# CHEAPO3.net
KiCad netlist of a schematic drawn in EAGLE
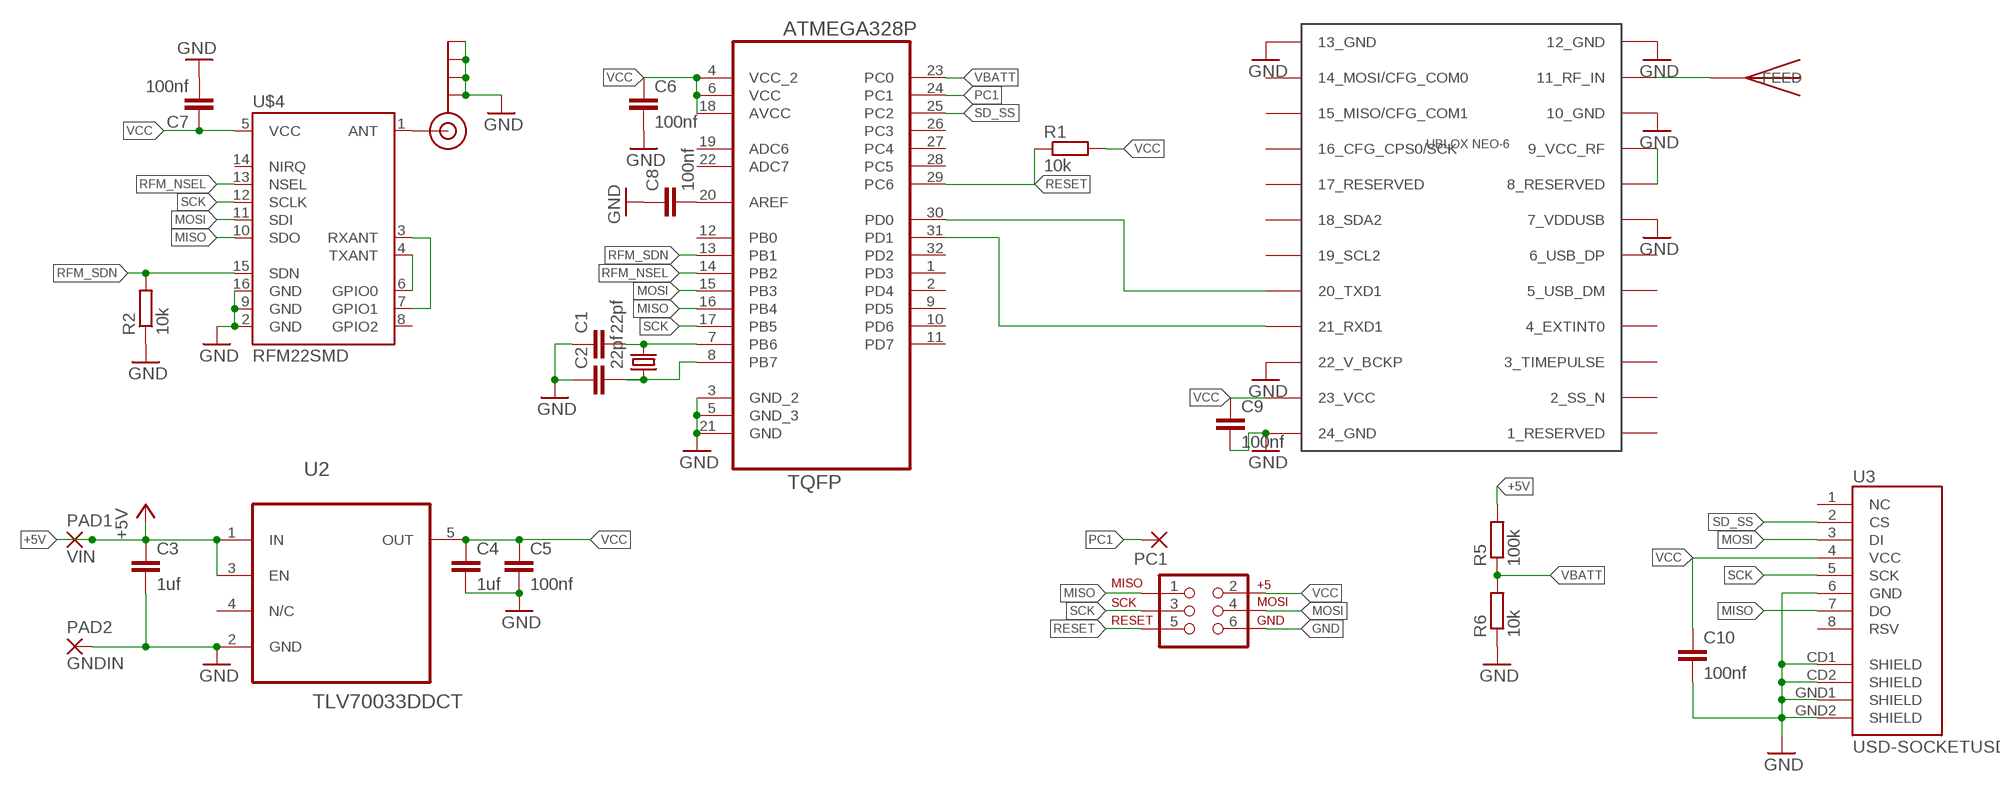
[diagram p0: schematic, sheet 1]

(export (version "E")
  (design (tool "Eeschema 10.0.6"))
  (components
    (comp (ref "C1")
      (value "22pf")
      (footprint "eagle-import:C0603")
      (libsource (lib "eagle-import") (part "C-EUC0603"))
    )
    (comp (ref "C2")
      (value "22pf")
      (footprint "eagle-import:C0603")
      (libsource (lib "eagle-import") (part "C-EUC0603"))
    )
    (comp (ref "C3")
      (value "1uf")
      (footprint "eagle-import:C0603")
      (libsource (lib "eagle-import") (part "C-EUC0603"))
    )
    (comp (ref "C4")
      (value "1uf")
      (footprint "eagle-import:C0603")
      (libsource (lib "eagle-import") (part "C-EUC0603"))
    )
    (comp (ref "C5")
      (value "100nf")
      (footprint "eagle-import:C0603")
      (libsource (lib "eagle-import") (part "C-EUC0603"))
    )
    (comp (ref "C6")
      (value "100nf")
      (footprint "eagle-import:C0603")
      (libsource (lib "eagle-import") (part "C-EUC0603"))
    )
    (comp (ref "C7")
      (value "100nf")
      (footprint "eagle-import:C0603")
      (libsource (lib "eagle-import") (part "C-EUC0603"))
    )
    (comp (ref "C8")
      (value "100nf")
      (footprint "eagle-import:C0603")
      (libsource (lib "eagle-import") (part "C-EUC0603"))
    )
    (comp (ref "C9")
      (value "100nf")
      (footprint "eagle-import:C0603")
      (libsource (lib "eagle-import") (part "C-EUC0603"))
    )
    (comp (ref "C10")
      (value "100nf")
      (footprint "eagle-import:C0603")
      (libsource (lib "eagle-import") (part "C-EUC0603"))
    )
    (comp (ref "J$1")
      (value "SMA_EDGE")
      (footprint "eagle-import:SMA-EDGE")
      (libsource (lib "eagle-import") (part "SMA_EDGE"))
    )
    (comp (ref "J1")
      (value "AVR_SPI_PRG_6PTH")
      (footprint "eagle-import:2X3")
      (libsource (lib "eagle-import") (part "AVR_SPI_PRG_6PTH"))
    )
    (comp (ref "PAD1")
      (value "VIN")
      (footprint "eagle-import:SMD1,27-2,54")
      (libsource (lib "eagle-import") (part "SMD2"))
    )
    (comp (ref "PAD2")
      (value "GNDIN")
      (footprint "eagle-import:SMD1,27-2,54")
      (libsource (lib "eagle-import") (part "SMD2"))
    )
    (comp (ref "PC1")
      (value "SMD2")
      (footprint "eagle-import:SMD1,27-2,54")
      (libsource (lib "eagle-import") (part "SMD2"))
    )
    (comp (ref "R1")
      (value "10k")
      (footprint "eagle-import:R0603")
      (libsource (lib "eagle-import") (part "R-EU_R0603"))
    )
    (comp (ref "R2")
      (value "10k")
      (footprint "eagle-import:R0603")
      (libsource (lib "eagle-import") (part "R-EU_R0603"))
    )
    (comp (ref "R5")
      (value "100k")
      (footprint "eagle-import:R0603")
      (libsource (lib "eagle-import") (part "R-EU_R0603"))
    )
    (comp (ref "R6")
      (value "10k")
      (footprint "eagle-import:R0603")
      (libsource (lib "eagle-import") (part "R-EU_R0603"))
    )
    (comp (ref "U$1")
      (value "UBLOX_NEO-6")
      (footprint "eagle-import:UBLOX_NEO-6P")
      (libsource (lib "eagle-import") (part "UBLOX_NEO-6"))
    )
    (comp (ref "U$2")
      (value "ABRACON_ABM3_CRYSTALABM03_HC49")
      (footprint "eagle-import:ABM03_HC49")
      (libsource (lib "eagle-import") (part "ABRACON_ABM3_CRYSTALABM03_HC49"))
    )
    (comp (ref "U$3")
      (value "JTI_ANTENNA-1575AT43A40")
      (footprint "eagle-import:JTI_ANTENNA-1575AT43A40")
      (libsource (lib "eagle-import") (part "JTI_ANTENNA-1575AT43A40"))
    )
    (comp (ref "U$4")
      (value "RFM22SMD")
      (footprint "eagle-import:RFM22-XXX-S2")
      (libsource (lib "eagle-import") (part "RFM22SMD"))
    )
    (comp (ref "U1")
      (value "ATMEGA328P-AU")
      (footprint "eagle-import:QFP80P900X900X120-32N")
      (libsource (lib "eagle-import") (part "ATMEGA328P-AU"))
    )
    (comp (ref "U2")
      (value "TLV70033DDCT")
      (footprint "eagle-import:SOT95P280X110-5N")
      (libsource (lib "eagle-import") (part "TLV70033DDCT"))
    )
    (comp (ref "U3")
      (value "USD-SOCKETUSD")
      (footprint "eagle-import:USD-SOCKET-PP")
      (libsource (lib "eagle-import") (part "USD-SOCKETUSD"))
    )
  )
  (nets
    (net (code "1") (name "+5V") (class "Default")
      (node (ref "C3") (pin "1") (pinfunction "1_1") (pintype "passive"))
      (node (ref "PAD1") (pin "1") (pinfunction "P_1") (pintype "passive"))
      (node (ref "R5") (pin "2") (pinfunction "2_2") (pintype "passive"))
      (node (ref "U2") (pin "1") (pinfunction "IN_1") (pintype "input"))
      (node (ref "U2") (pin "3") (pinfunction "EN_3") (pintype "input"))
    )
    (net (code "2") (name "GND") (class "Default")
      (node (ref "C1") (pin "1") (pinfunction "1_1") (pintype "passive"))
      (node (ref "C10") (pin "2") (pinfunction "2_2") (pintype "passive"))
      (node (ref "C2") (pin "1") (pinfunction "1_1") (pintype "passive"))
      (node (ref "C3") (pin "2") (pinfunction "2_2") (pintype "passive"))
      (node (ref "C4") (pin "2") (pinfunction "2_2") (pintype "passive"))
      (node (ref "C5") (pin "2") (pinfunction "2_2") (pintype "passive"))
      (node (ref "C6") (pin "2") (pinfunction "2_2") (pintype "passive"))
      (node (ref "C7") (pin "2") (pinfunction "2_2") (pintype "passive"))
      (node (ref "C8") (pin "1") (pinfunction "1_1") (pintype "passive"))
      (node (ref "C9") (pin "2") (pinfunction "2_2") (pintype "passive"))
      (node (ref "J$1") (pin "GND@0") (pinfunction "GND_GND@0") (pintype "bidirectional"))
      (node (ref "J$1") (pin "GND@1") (pinfunction "GND_GND@1") (pintype "bidirectional"))
      (node (ref "J$1") (pin "GND@2") (pinfunction "GND_GND@2") (pintype "bidirectional"))
      (node (ref "J$1") (pin "GND@3") (pinfunction "GND_GND@3") (pintype "bidirectional"))
      (node (ref "J1") (pin "6") (pinfunction "6_6") (pintype "passive"))
      (node (ref "PAD2") (pin "1") (pinfunction "P_1") (pintype "passive"))
      (node (ref "R2") (pin "1") (pinfunction "1_1") (pintype "passive"))
      (node (ref "R6") (pin "1") (pinfunction "1_1") (pintype "passive"))
      (node (ref "U$1") (pin "10_GND") (pinfunction "10_GND_10_GND") (pintype "bidirectional"))
      (node (ref "U$1") (pin "12_GND") (pinfunction "12_GND_12_GND") (pintype "bidirectional"))
      (node (ref "U$1") (pin "13_GND") (pinfunction "13_GND_13_GND") (pintype "bidirectional"))
      (node (ref "U$1") (pin "22_V_BCKP") (pinfunction "22_V_BCKP_22_V_BCKP") (pintype "bidirectional"))
      (node (ref "U$1") (pin "24_GND") (pinfunction "24_GND_24_GND") (pintype "bidirectional"))
      (node (ref "U$1") (pin "7_VDDUSB") (pinfunction "7_VDDUSB_7_VDDUSB") (pintype "bidirectional"))
      (node (ref "U$4") (pin "16") (pinfunction "GND_16") (pintype "power_in"))
      (node (ref "U$4") (pin "2") (pinfunction "GND_2") (pintype "power_in"))
      (node (ref "U$4") (pin "9") (pinfunction "GND_9") (pintype "power_in"))
      (node (ref "U1") (pin "21") (pinfunction "GND_21") (pintype "passive"))
      (node (ref "U1") (pin "3") (pinfunction "GND_2_3") (pintype "passive"))
      (node (ref "U1") (pin "5") (pinfunction "GND_3_5") (pintype "passive"))
      (node (ref "U2") (pin "2") (pinfunction "GND_2") (pintype "passive"))
      (node (ref "U3") (pin "6") (pinfunction "GND_6") (pintype "bidirectional"))
      (node (ref "U3") (pin "CD1") (pinfunction "SHIELD_CD1") (pintype "bidirectional"))
      (node (ref "U3") (pin "CD2") (pinfunction "SHIELD_CD2") (pintype "bidirectional"))
      (node (ref "U3") (pin "GND1") (pinfunction "SHIELD_GND1") (pintype "bidirectional"))
      (node (ref "U3") (pin "GND2") (pinfunction "SHIELD_GND2") (pintype "bidirectional"))
    )
    (net (code "3") (name "MISO") (class "Default")
      (node (ref "J1") (pin "1") (pinfunction "1_1") (pintype "passive"))
      (node (ref "U$4") (pin "10") (pinfunction "SDO_10") (pintype "output"))
      (node (ref "U1") (pin "16") (pinfunction "PB4_16") (pintype "bidirectional"))
      (node (ref "U3") (pin "7") (pinfunction "DO_7") (pintype "bidirectional"))
    )
    (net (code "4") (name "MOSI") (class "Default")
      (node (ref "J1") (pin "4") (pinfunction "4_4") (pintype "passive"))
      (node (ref "U$4") (pin "11") (pinfunction "SDI_11") (pintype "input"))
      (node (ref "U1") (pin "15") (pinfunction "PB3_15") (pintype "bidirectional"))
      (node (ref "U3") (pin "3") (pinfunction "DI_3") (pintype "bidirectional"))
    )
    (net (code "5") (name "Net-(J$1-SIGNAL)") (class "Default")
      (node (ref "J$1") (pin "SIG") (pinfunction "SIGNAL_SIG") (pintype "bidirectional"))
      (node (ref "U$4") (pin "1") (pinfunction "ANT_1") (pintype "bidirectional"))
    )
    (net (code "6") (name "Net-(U$1-Pad8_RESERVED)") (class "Default")
      (node (ref "U$1") (pin "8_RESERVED") (pinfunction "8_RESERVED_8_RESERVED") (pintype "bidirectional"))
      (node (ref "U$1") (pin "9_VCC_RF") (pinfunction "9_VCC_RF_9_VCC_RF") (pintype "bidirectional"))
    )
    (net (code "7") (name "Net-(U$1-Pad11_RF_IN)") (class "Default")
      (node (ref "U$1") (pin "11_RF_IN") (pinfunction "11_RF_IN_11_RF_IN") (pintype "bidirectional"))
      (node (ref "U$3") (pin "FEED") (pinfunction "FEED_FEED") (pintype "bidirectional"))
    )
    (net (code "8") (name "Net-(U$4-GPIO0)") (class "Default")
      (node (ref "U$4") (pin "4") (pinfunction "TXANT_4") (pintype "input"))
      (node (ref "U$4") (pin "6") (pinfunction "GPIO0_6") (pintype "bidirectional"))
    )
    (net (code "9") (name "Net-(U$4-GPIO1)") (class "Default")
      (node (ref "U$4") (pin "3") (pinfunction "RXANT_3") (pintype "input"))
      (node (ref "U$4") (pin "7") (pinfunction "GPIO1_7") (pintype "bidirectional"))
    )
    (net (code "10") (name "Net-(U1-AREF)") (class "Default")
      (node (ref "C8") (pin "2") (pinfunction "2_2") (pintype "passive"))
      (node (ref "U1") (pin "20") (pinfunction "AREF_20") (pintype "input"))
    )
    (net (code "11") (name "Net-(U1-PB6)") (class "Default")
      (node (ref "C1") (pin "2") (pinfunction "2_2") (pintype "passive"))
      (node (ref "U$2") (pin "2") (pinfunction "2_2") (pintype "passive"))
      (node (ref "U1") (pin "7") (pinfunction "PB6_7") (pintype "bidirectional"))
    )
    (net (code "12") (name "Net-(U1-PB7)") (class "Default")
      (node (ref "C2") (pin "2") (pinfunction "2_2") (pintype "passive"))
      (node (ref "U$2") (pin "1") (pinfunction "1_1") (pintype "passive"))
      (node (ref "U1") (pin "8") (pinfunction "PB7_8") (pintype "bidirectional"))
    )
    (net (code "13") (name "Net-(U1-PD0)") (class "Default")
      (node (ref "U$1") (pin "20_TXD1") (pinfunction "20_TXD1_20_TXD1") (pintype "bidirectional"))
      (node (ref "U1") (pin "30") (pinfunction "PD0_30") (pintype "bidirectional"))
    )
    (net (code "14") (name "Net-(U1-PD1)") (class "Default")
      (node (ref "U$1") (pin "21_RXD1") (pinfunction "21_RXD1_21_RXD1") (pintype "bidirectional"))
      (node (ref "U1") (pin "31") (pinfunction "PD1_31") (pintype "bidirectional"))
    )
    (net (code "15") (name "PC1") (class "Default")
      (node (ref "PC1") (pin "1") (pinfunction "P_1") (pintype "passive"))
      (node (ref "U1") (pin "24") (pinfunction "PC1_24") (pintype "bidirectional"))
    )
    (net (code "16") (name "RESET") (class "Default")
      (node (ref "J1") (pin "5") (pinfunction "5_5") (pintype "passive"))
      (node (ref "R1") (pin "1") (pinfunction "1_1") (pintype "passive"))
      (node (ref "U1") (pin "29") (pinfunction "PC6_29") (pintype "bidirectional"))
    )
    (net (code "17") (name "RFM_NSEL") (class "Default")
      (node (ref "U$4") (pin "13") (pinfunction "NSEL_13") (pintype "input"))
      (node (ref "U1") (pin "14") (pinfunction "PB2_14") (pintype "bidirectional"))
    )
    (net (code "18") (name "RFM_SDN") (class "Default")
      (node (ref "R2") (pin "2") (pinfunction "2_2") (pintype "passive"))
      (node (ref "U$4") (pin "15") (pinfunction "SDN_15") (pintype "input"))
      (node (ref "U1") (pin "13") (pinfunction "PB1_13") (pintype "bidirectional"))
    )
    (net (code "19") (name "SCK") (class "Default")
      (node (ref "J1") (pin "3") (pinfunction "3_3") (pintype "passive"))
      (node (ref "U$4") (pin "12") (pinfunction "SCLK_12") (pintype "input"))
      (node (ref "U1") (pin "17") (pinfunction "PB5_17") (pintype "bidirectional"))
      (node (ref "U3") (pin "5") (pinfunction "SCK_5") (pintype "bidirectional"))
    )
    (net (code "20") (name "SD_SS") (class "Default")
      (node (ref "U1") (pin "25") (pinfunction "PC2_25") (pintype "bidirectional"))
      (node (ref "U3") (pin "2") (pinfunction "CS_2") (pintype "bidirectional"))
    )
    (net (code "21") (name "VBATT") (class "Default")
      (node (ref "R5") (pin "1") (pinfunction "1_1") (pintype "passive"))
      (node (ref "R6") (pin "2") (pinfunction "2_2") (pintype "passive"))
      (node (ref "U1") (pin "23") (pinfunction "PC0_23") (pintype "bidirectional"))
    )
    (net (code "22") (name "VCC") (class "Default")
      (node (ref "C10") (pin "1") (pinfunction "1_1") (pintype "passive"))
      (node (ref "C4") (pin "1") (pinfunction "1_1") (pintype "passive"))
      (node (ref "C5") (pin "1") (pinfunction "1_1") (pintype "passive"))
      (node (ref "C6") (pin "1") (pinfunction "1_1") (pintype "passive"))
      (node (ref "C7") (pin "1") (pinfunction "1_1") (pintype "passive"))
      (node (ref "C9") (pin "1") (pinfunction "1_1") (pintype "passive"))
      (node (ref "J1") (pin "2") (pinfunction "2_2") (pintype "passive"))
      (node (ref "R1") (pin "2") (pinfunction "2_2") (pintype "passive"))
      (node (ref "U$1") (pin "23_VCC") (pinfunction "23_VCC_23_VCC") (pintype "bidirectional"))
      (node (ref "U$4") (pin "5") (pinfunction "VCC_5") (pintype "bidirectional"))
      (node (ref "U1") (pin "18") (pinfunction "AVCC_18") (pintype "power_in"))
      (node (ref "U1") (pin "4") (pinfunction "VCC_2_4") (pintype "power_in"))
      (node (ref "U1") (pin "6") (pinfunction "VCC_6") (pintype "power_in"))
      (node (ref "U2") (pin "5") (pinfunction "OUT_5") (pintype "output"))
      (node (ref "U3") (pin "4") (pinfunction "VCC_4") (pintype "bidirectional"))
    )
    (net (code "23") (name "unconnected-(U$1-Pad1_RESERVED)") (class "Default")
      (node (ref "U$1") (pin "1_RESERVED") (pinfunction "1_RESERVED_1_RESERVED") (pintype "bidirectional"))
    )
    (net (code "24") (name "unconnected-(U$1-Pad2_SS_N)") (class "Default")
      (node (ref "U$1") (pin "2_SS_N") (pinfunction "2_SS_N_2_SS_N") (pintype "bidirectional"))
    )
    (net (code "25") (name "unconnected-(U$1-Pad3_TIMEPULSE)") (class "Default")
      (node (ref "U$1") (pin "3_TIMEPULSE") (pinfunction "3_TIMEPULSE_3_TIMEPULSE") (pintype "bidirectional"))
    )
    (net (code "26") (name "unconnected-(U$1-Pad4_EXTINT0)") (class "Default")
      (node (ref "U$1") (pin "4_EXTINT0") (pinfunction "4_EXTINT0_4_EXTINT0") (pintype "bidirectional"))
    )
    (net (code "27") (name "unconnected-(U$1-Pad5_USB_DM)") (class "Default")
      (node (ref "U$1") (pin "5_USB_DM") (pinfunction "5_USB_DM_5_USB_DM") (pintype "bidirectional"))
    )
    (net (code "28") (name "unconnected-(U$1-Pad6_USB_DP)") (class "Default")
      (node (ref "U$1") (pin "6_USB_DP") (pinfunction "6_USB_DP_6_USB_DP") (pintype "bidirectional"))
    )
    (net (code "29") (name "unconnected-(U$1-Pad14_MOSI{slash}CFG_COM0)") (class "Default")
      (node (ref "U$1") (pin "14_MOSI/CFG_COM0") (pinfunction "14_MOSI/CFG_COM0_14_MOSI/CFG_COM0") (pintype "bidirectional"))
    )
    (net (code "30") (name "unconnected-(U$1-Pad15_MISO{slash}CFG_COM1)") (class "Default")
      (node (ref "U$1") (pin "15_MISO/CFG_COM1") (pinfunction "15_MISO/CFG_COM1_15_MISO/CFG_COM1") (pintype "bidirectional"))
    )
    (net (code "31") (name "unconnected-(U$1-Pad16_CFG_CPS0{slash}SCK)") (class "Default")
      (node (ref "U$1") (pin "16_CFG_CPS0/SCK") (pinfunction "16_CFG_CPS0/SCK_16_CFG_CPS0/SCK") (pintype "bidirectional"))
    )
    (net (code "32") (name "unconnected-(U$1-Pad17_RESERVED)") (class "Default")
      (node (ref "U$1") (pin "17_RESERVED") (pinfunction "17_RESERVED_17_RESERVED") (pintype "bidirectional"))
    )
    (net (code "33") (name "unconnected-(U$1-Pad18_SDA2)") (class "Default")
      (node (ref "U$1") (pin "18_SDA2") (pinfunction "18_SDA2_18_SDA2") (pintype "bidirectional"))
    )
    (net (code "34") (name "unconnected-(U$1-Pad19_SCL2)") (class "Default")
      (node (ref "U$1") (pin "19_SCL2") (pinfunction "19_SCL2_19_SCL2") (pintype "bidirectional"))
    )
    (net (code "35") (name "unconnected-(U$4-GPIO2-Pad8)") (class "Default")
      (node (ref "U$4") (pin "8") (pinfunction "GPIO2_8") (pintype "bidirectional"))
    )
    (net (code "36") (name "unconnected-(U$4-NIRQ-Pad14)") (class "Default")
      (node (ref "U$4") (pin "14") (pinfunction "NIRQ_14") (pintype "output"))
    )
    (net (code "37") (name "unconnected-(U1-ADC6-Pad19)") (class "Default")
      (node (ref "U1") (pin "19") (pinfunction "ADC6_19") (pintype "input"))
    )
    (net (code "38") (name "unconnected-(U1-ADC7-Pad22)") (class "Default")
      (node (ref "U1") (pin "22") (pinfunction "ADC7_22") (pintype "input"))
    )
    (net (code "39") (name "unconnected-(U1-PB0-Pad12)") (class "Default")
      (node (ref "U1") (pin "12") (pinfunction "PB0_12") (pintype "bidirectional"))
    )
    (net (code "40") (name "unconnected-(U1-PC3-Pad26)") (class "Default")
      (node (ref "U1") (pin "26") (pinfunction "PC3_26") (pintype "bidirectional"))
    )
    (net (code "41") (name "unconnected-(U1-PC4-Pad27)") (class "Default")
      (node (ref "U1") (pin "27") (pinfunction "PC4_27") (pintype "bidirectional"))
    )
    (net (code "42") (name "unconnected-(U1-PC5-Pad28)") (class "Default")
      (node (ref "U1") (pin "28") (pinfunction "PC5_28") (pintype "bidirectional"))
    )
    (net (code "43") (name "unconnected-(U1-PD2-Pad32)") (class "Default")
      (node (ref "U1") (pin "32") (pinfunction "PD2_32") (pintype "bidirectional"))
    )
    (net (code "44") (name "unconnected-(U1-PD3-Pad1)") (class "Default")
      (node (ref "U1") (pin "1") (pinfunction "PD3_1") (pintype "bidirectional"))
    )
    (net (code "45") (name "unconnected-(U1-PD4-Pad2)") (class "Default")
      (node (ref "U1") (pin "2") (pinfunction "PD4_2") (pintype "bidirectional"))
    )
    (net (code "46") (name "unconnected-(U1-PD5-Pad9)") (class "Default")
      (node (ref "U1") (pin "9") (pinfunction "PD5_9") (pintype "bidirectional"))
    )
    (net (code "47") (name "unconnected-(U1-PD6-Pad10)") (class "Default")
      (node (ref "U1") (pin "10") (pinfunction "PD6_10") (pintype "bidirectional"))
    )
    (net (code "48") (name "unconnected-(U1-PD7-Pad11)") (class "Default")
      (node (ref "U1") (pin "11") (pinfunction "PD7_11") (pintype "bidirectional"))
    )
    (net (code "49") (name "unconnected-(U2-N{slash}C-Pad4)") (class "Default")
      (node (ref "U2") (pin "4") (pinfunction "N/C_4") (pintype "no_connect"))
    )
    (net (code "50") (name "unconnected-(U3-NC-Pad1)") (class "Default")
      (node (ref "U3") (pin "1") (pinfunction "NC_1") (pintype "bidirectional"))
    )
    (net (code "51") (name "unconnected-(U3-RSV-Pad8)") (class "Default")
      (node (ref "U3") (pin "8") (pinfunction "RSV_8") (pintype "bidirectional"))
    )
  )
)
